# uC_HMI.net
KiCad netlist of a schematic drawn in Altium Designer
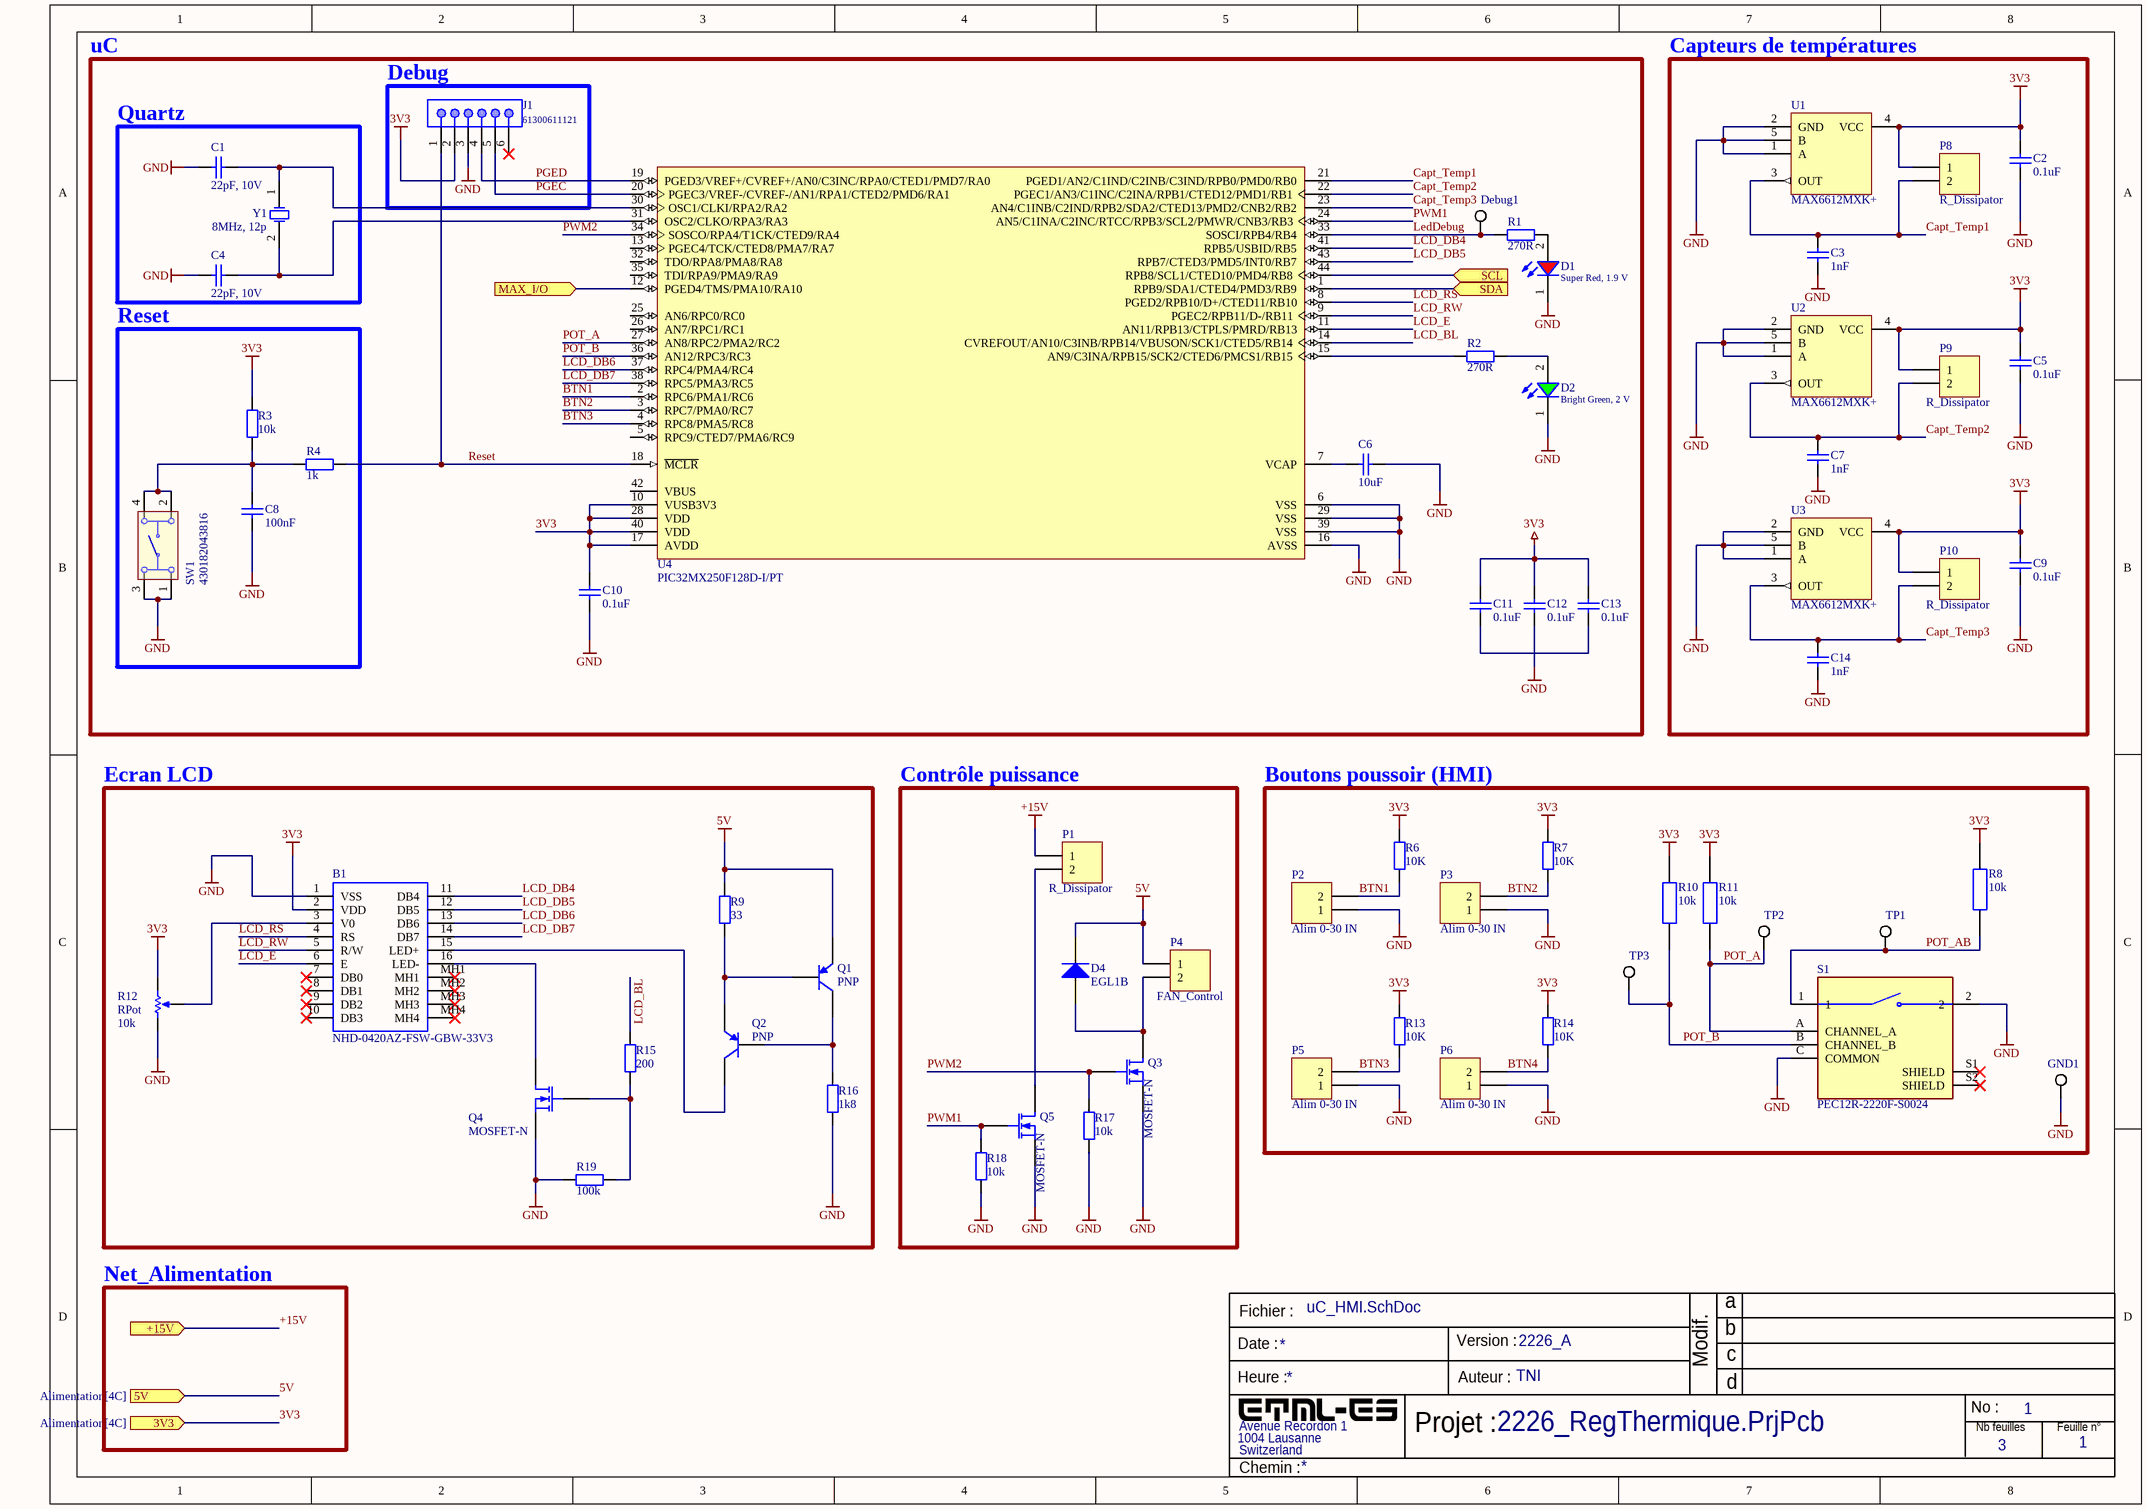
[diagram p0: uC_HMI.SchDoc]

(export (version "E")
  (design (tool "Eeschema 10.0.6"))
  (components
    (comp (ref "B1")
      (value "NHD-0420AZ-FSW-GBW-33V3")
      (footprint "NHD0420AZFSWGBW33V3")
      (description "LCD Character Display Modules & Accessories STN- GRAY Transfl 77.5 x 47.0")
      (fields (field (name "MOUSER PART NUMBER") "763-0420AZFSWGBW33V3"))
      (libsource (lib "NHD-0420AZ-FSW-GBW-33V3") (part "NHD-0420AZ-FSW-GBW-33V3"))
    )
    (comp (ref "C1")
      (value "22pF, 10V")
      (footprint "6-0805_L")
      (description "CAP 22pF 10V")
      (fields (field (name "TOLERANCE") "Â±10%"))
      (libsource (lib "2121_Robot3roues_V2.0") (part "CAP"))
    )
    (comp (ref "C2")
      (value "0.1uF")
      (footprint "C0805")
      (description "Cap 100nF")
      (fields (field (name "Comment") "Cap") (field (name "PUBLISHER") "Altium Limited"))
      (libsource (lib "Miscellaneous Devices") (part "Cap"))
    )
    (comp (ref "C3")
      (value "1nF")
      (footprint "C0805")
      (description "Cap 1nF")
      (fields (field (name "Comment") "Cap") (field (name "PUBLISHER") "Altium Limited"))
      (libsource (lib "Miscellaneous Devices") (part "Cap"))
    )
    (comp (ref "C4")
      (value "22pF, 10V")
      (footprint "6-0805_L")
      (description "CAP 22pF 10V")
      (fields (field (name "TOLERANCE") "Â±10%"))
      (libsource (lib "2121_Robot3roues_V2.0") (part "CAP"))
    )
    (comp (ref "C5")
      (value "0.1uF")
      (footprint "C0805")
      (description "Cap 100nF")
      (fields (field (name "Comment") "Cap") (field (name "PUBLISHER") "Altium Limited"))
      (libsource (lib "Miscellaneous Devices") (part "Cap"))
    )
    (comp (ref "C6")
      (value "10uF")
      (footprint "C0805")
      (description "Cap 100nF")
      (fields (field (name "Comment") "Cap") (field (name "PUBLISHER") "Altium Limited"))
      (libsource (lib "Miscellaneous Devices") (part "Cap"))
    )
    (comp (ref "C7")
      (value "1nF")
      (footprint "C0805")
      (description "Cap 1nF")
      (fields (field (name "Comment") "Cap") (field (name "PUBLISHER") "Altium Limited"))
      (libsource (lib "Miscellaneous Devices") (part "Cap"))
    )
    (comp (ref "C8")
      (value "100nF")
      (footprint "C0805")
      (description "Cap 100nF")
      (fields (field (name "Comment") "Cap") (field (name "PUBLISHER") "Altium Limited"))
      (libsource (lib "Miscellaneous Devices") (part "Cap"))
    )
    (comp (ref "C9")
      (value "0.1uF")
      (footprint "C0805")
      (description "Cap 100nF")
      (fields (field (name "Comment") "Cap") (field (name "PUBLISHER") "Altium Limited"))
      (libsource (lib "Miscellaneous Devices") (part "Cap"))
    )
    (comp (ref "C10")
      (value "0.1uF")
      (footprint "C0805")
      (description "Cap 100nF")
      (fields (field (name "Comment") "Cap") (field (name "PUBLISHER") "Altium Limited"))
      (libsource (lib "Miscellaneous Devices") (part "Cap"))
    )
    (comp (ref "C11")
      (value "0.1uF")
      (footprint "C0805")
      (description "Cap 100nF")
      (fields (field (name "Comment") "Cap") (field (name "PUBLISHER") "Altium Limited"))
      (libsource (lib "Miscellaneous Devices") (part "Cap"))
    )
    (comp (ref "C12")
      (value "0.1uF")
      (footprint "C0805")
      (description "Cap 100nF")
      (fields (field (name "Comment") "Cap") (field (name "PUBLISHER") "Altium Limited"))
      (libsource (lib "Miscellaneous Devices") (part "Cap"))
    )
    (comp (ref "C13")
      (value "0.1uF")
      (footprint "C0805")
      (description "Cap 100nF")
      (fields (field (name "Comment") "Cap") (field (name "PUBLISHER") "Altium Limited"))
      (libsource (lib "Miscellaneous Devices") (part "Cap"))
    )
    (comp (ref "C14")
      (value "1nF")
      (footprint "C0805")
      (description "Cap 1nF")
      (fields (field (name "Comment") "Cap") (field (name "PUBLISHER") "Altium Limited"))
      (libsource (lib "Miscellaneous Devices") (part "Cap"))
    )
    (comp (ref "D1")
      (value "Super Red, 1.9 V")
      (footprint "6-0805_N")
      (description "SMT Mono-color Chip LED Waterclear WL-SMCW, size 0805, Super Red, 1.9 V, 140 deg, 60 mcd")
      (fields (field (name "PART NUMBER") "150080SS75000") (field (name "PUBLISHER") "Wurth Elektronik"))
      (libsource (lib "VPA_v2b") (part "150080SS75000"))
    )
    (comp (ref "D2")
      (value "Bright Green, 2 V")
      (footprint "6-0805_N")
      (description "SMT Mono-color Chip LED Waterclear WL-SMCW, size 0805, Bright Green, 2 V, 140 deg, 40 mcd")
      (fields (field (name "PART NUMBER") "150080VS75000") (field (name "PUBLISHER") "Wurth Elektronik"))
      (libsource (lib "VPA_v2b") (part "150080VS75000"))
    )
    (comp (ref "D4")
      (value "EGL1B")
      (footprint "JAN1N4108CUR1_")
      (description "Diode Melf : EGL1B (100V,1A)")
      (fields (field (name "PUBLISHER") "Altium Limited"))
      (libsource (lib "Miscellaneous Devices") (part "Diode"))
    )
    (comp (ref "Debug1")
      (value "LedDebugg")
      (footprint "KSTN-5019_V")
      (description "Test Point, 1 Position SMD, RoHS, Tape and Reel")
      (libsource (lib "Altium Content Vault") (part "TESTPOINT_WHITE"))
    )
    (comp (ref "GND1")
      (value "PEC12")
      (footprint "KSTN-5019_V")
      (description "Test Point, 1 Position SMD, RoHS, Tape and Reel")
      (libsource (lib "Altium Content Vault") (part "TESTPOINT_WHITE"))
    )
    (comp (ref "J1")
      (value "61300611121")
      (footprint "HDR1X6")
      (description "WR-PHD Pin Header, THT, pitch 2.54mm, Single Row, Vertical, 6pin")
      (fields (field (name "PUBLISHER") "Wurth Elektronik"))
      (libsource (lib "VPA_v2b") (part "61300611121"))
    )
    (comp (ref "P1")
      (value "R_Dissipator")
      (footprint "RHDRRA2W95P0X500_1X2_1120X900X1280P")
      (description "Header, 2-Pin")
      (fields (field (name "PUBLISHER") "Altium Limited"))
      (libsource (lib "Miscellaneous Connectors") (part "Header 2"))
    )
    (comp (ref "P2")
      (value "Alim 0-30 IN")
      (footprint "HDR1X2")
      (description "Header, 2-Pin")
      (fields (field (name "PUBLISHER") "Altium Limited"))
      (libsource (lib "") (part "Header 2_1"))
    )
    (comp (ref "P3")
      (value "Alim 0-30 IN")
      (footprint "HDR1X2")
      (description "Header, 2-Pin")
      (fields (field (name "PUBLISHER") "Altium Limited"))
      (libsource (lib "") (part "Header 2_1"))
    )
    (comp (ref "P4")
      (value "FAN_Control")
      (footprint "RHDRRA2W95P0X500_1X2_1120X900X1280P")
      (description "Header, 2-Pin")
      (fields (field (name "PUBLISHER") "Altium Limited"))
      (libsource (lib "Miscellaneous Connectors") (part "Header 2"))
    )
    (comp (ref "P5")
      (value "Alim 0-30 IN")
      (footprint "HDR1X2")
      (description "Header, 2-Pin")
      (fields (field (name "PUBLISHER") "Altium Limited"))
      (libsource (lib "") (part "Header 2_1"))
    )
    (comp (ref "P6")
      (value "Alim 0-30 IN")
      (footprint "HDR1X2")
      (description "Header, 2-Pin")
      (fields (field (name "PUBLISHER") "Altium Limited"))
      (libsource (lib "") (part "Header 2_1"))
    )
    (comp (ref "P8")
      (value "R_Dissipator")
      (footprint "RHDRRA2W95P0X500_1X2_1120X900X1280P")
      (description "Header, 2-Pin")
      (fields (field (name "PUBLISHER") "Altium Limited"))
      (libsource (lib "Miscellaneous Connectors") (part "Header 2"))
    )
    (comp (ref "P9")
      (value "R_Dissipator")
      (footprint "RHDRRA2W95P0X500_1X2_1120X900X1280P")
      (description "Header, 2-Pin")
      (fields (field (name "PUBLISHER") "Altium Limited"))
      (libsource (lib "Miscellaneous Connectors") (part "Header 2"))
    )
    (comp (ref "P10")
      (value "R_Dissipator")
      (footprint "RHDRRA2W95P0X500_1X2_1120X900X1280P")
      (description "Header, 2-Pin")
      (fields (field (name "PUBLISHER") "Altium Limited"))
      (libsource (lib "Miscellaneous Connectors") (part "Header 2"))
    )
    (comp (ref "Q1")
      (value "PNP")
      (footprint "SOT-23B_N")
      (description "PNP Bipolar Transistor")
      (fields (field (name "PUBLISHER") "Altium Limited"))
      (libsource (lib "Miscellaneous Devices") (part "PNP"))
    )
    (comp (ref "Q2")
      (value "PNP")
      (footprint "SOT-23B_N")
      (description "PNP Bipolar Transistor")
      (fields (field (name "PUBLISHER") "Altium Limited"))
      (libsource (lib "Miscellaneous Devices") (part "PNP"))
    )
    (comp (ref "Q3")
      (value "MOSFET-N")
      (footprint "SOT23_N")
      (description "N-Channel MOSFET")
      (fields (field (name "PUBLISHER") "Altium Limited"))
      (libsource (lib "Miscellaneous Devices") (part "MOSFET-N"))
    )
    (comp (ref "Q4")
      (value "MOSFET-N")
      (footprint "SOT23_N")
      (description "N-Channel MOSFET")
      (fields (field (name "PUBLISHER") "Altium Limited"))
      (libsource (lib "Miscellaneous Devices") (part "MOSFET-N"))
    )
    (comp (ref "Q5")
      (value "MOSFET-N")
      (footprint "SOT23_N")
      (description "N-Channel MOSFET")
      (fields (field (name "PUBLISHER") "Altium Limited"))
      (libsource (lib "Miscellaneous Devices") (part "MOSFET-N"))
    )
    (comp (ref "R1")
      (value "270R")
      (footprint "6-0805_N")
      (description "Res 270R")
      (fields (field (name "PART NUMBER") "ERJ6ENF2703V") (field (name "MANUFACTURER") "Panasonic"))
      (libsource (lib "2121_Robot3roues_V2.0") (part "RES"))
    )
    (comp (ref "R2")
      (value "270R")
      (footprint "6-0805_N")
      (description "Res 270R")
      (fields (field (name "PART NUMBER") "ERJ6ENF2703V") (field (name "MANUFACTURER") "Panasonic"))
      (libsource (lib "2121_Robot3roues_V2.0") (part "RES"))
    )
    (comp (ref "R3")
      (value "10k")
      (footprint "6-0805_N")
      (description "Res 10K")
      (fields (field (name "MANUFACTURER") "Panasonic") (field (name "PART NUMBER") "ERJ-6ENF1002V"))
      (libsource (lib "") (part "RES_2"))
    )
    (comp (ref "R4")
      (value "1k")
      (footprint "6-0805_N")
      (description "Res 1K")
      (fields (field (name "PART NUMBER") "CRCW08051K00FKEA") (field (name "MANUFACTURER") "Vishay Dale"))
      (libsource (lib "") (part "RES_1"))
    )
    (comp (ref "R6")
      (value "10K")
      (footprint "6-0805_N")
      (description "Res 10K")
      (fields (field (name "PUBLISHER") "Altium Limited"))
      (libsource (lib "Miscellaneous Devices") (part "Res2"))
    )
    (comp (ref "R7")
      (value "10K")
      (footprint "6-0805_N")
      (description "Res 10K")
      (fields (field (name "PUBLISHER") "Altium Limited"))
      (libsource (lib "Miscellaneous Devices") (part "Res2"))
    )
    (comp (ref "R8")
      (value "10k")
      (footprint "6-0805_N")
      (description "Res 10K")
      (libsource (lib "2019_RegThermiqueMyRio") (part "Resistor"))
    )
    (comp (ref "R9")
      (value "33")
      (footprint "6-0805_N")
      (description "Res 33R")
      (fields (field (name "Comment") "Res2") (field (name "PUBLISHER") "Altium Limited"))
      (libsource (lib "") (part "Res2_2"))
    )
    (comp (ref "R10")
      (value "10k")
      (footprint "6-0805_N")
      (description "Res 10K")
      (libsource (lib "2019_RegThermiqueMyRio") (part "Resistor"))
    )
    (comp (ref "R11")
      (value "10k")
      (footprint "6-0805_N")
      (description "Res 10K")
      (libsource (lib "2019_RegThermiqueMyRio") (part "Resistor"))
    )
    (comp (ref "R12")
      (value "RPot")
      (footprint "3362P_1")
      (description "Pot 10K")
      (fields (field (name "ALTIUM_VALUE") "10k") (field (name "PUBLISHER") "Altium Limited"))
      (libsource (lib "Miscellaneous Devices") (part "RPot"))
    )
    (comp (ref "R13")
      (value "10K")
      (footprint "6-0805_N")
      (description "Res 10K")
      (fields (field (name "PUBLISHER") "Altium Limited"))
      (libsource (lib "Miscellaneous Devices") (part "Res2"))
    )
    (comp (ref "R14")
      (value "10K")
      (footprint "6-0805_N")
      (description "Res 10K")
      (fields (field (name "PUBLISHER") "Altium Limited"))
      (libsource (lib "Miscellaneous Devices") (part "Res2"))
    )
    (comp (ref "R15")
      (value "200")
      (footprint "6-0805_N")
      (description "Res 200R")
      (fields (field (name "Comment") "Res2") (field (name "PUBLISHER") "Altium Limited"))
      (libsource (lib "") (part "Res2_2"))
    )
    (comp (ref "R16")
      (value "1k8")
      (footprint "6-0805_N")
      (description "Res 1K8")
      (fields (field (name "Comment") "Res2") (field (name "PUBLISHER") "Altium Limited"))
      (libsource (lib "") (part "Res2_2"))
    )
    (comp (ref "R17")
      (value "10k")
      (footprint "6-0805_N")
      (description "Res 10K")
      (fields (field (name "Comment") "Res2") (field (name "PUBLISHER") "Altium Limited"))
      (libsource (lib "Miscellaneous Devices") (part "Res2"))
    )
    (comp (ref "R18")
      (value "10k")
      (footprint "6-0805_N")
      (description "Res 10K")
      (fields (field (name "Comment") "Res2") (field (name "PUBLISHER") "Altium Limited"))
      (libsource (lib "Miscellaneous Devices") (part "Res2"))
    )
    (comp (ref "R19")
      (value "100k")
      (footprint "6-0805_N")
      (description "Res 100K")
      (fields (field (name "Comment") "Res2") (field (name "PUBLISHER") "Altium Limited"))
      (libsource (lib "") (part "Res2_1"))
    )
    (comp (ref "S1")
      (value "PEC12R-2220F-S0024")
      (footprint "XDCR_PEC12R-2220F-S0024")
      (description "Rotary Encoder Mechanical 24 Quadrature (Incremental) Right Angle")
      (fields (field (name "MF") "Bourns"))
      (libsource (lib "2226_RegThermique") (part "PEC12R-2220F-S0024"))
    )
    (comp (ref "SW1")
      (value "430182043816")
      (footprint "430182043816")
      (description "WS-TASV SMD Tact Switch 6X6 mm")
      (fields (field (name "MANUFACTURER") "Wuerth Elektronik"))
      (libsource (lib "Altium Content Vault") (part "WE-TACT-SW-4"))
    )
    (comp (ref "TP1")
      (value "REGP")
      (footprint "KSTN-5019_V")
      (description "Test Point, 1 Position SMD, RoHS, Tape and Reel")
      (libsource (lib "Altium Content Vault") (part "TESTPOINT_WHITE"))
    )
    (comp (ref "TP2")
      (value "REGP")
      (footprint "KSTN-5019_V")
      (description "Test Point, 1 Position SMD, RoHS, Tape and Reel")
      (libsource (lib "Altium Content Vault") (part "TESTPOINT_WHITE"))
    )
    (comp (ref "TP3")
      (value "REGP")
      (footprint "KSTN-5019_V")
      (description "Test Point, 1 Position SMD, RoHS, Tape and Reel")
      (libsource (lib "Altium Content Vault") (part "TESTPOINT_WHITE"))
    )
    (comp (ref "U1")
      (value "MAX6612MXK+")
      (footprint "MAXM-X5+1_M")
      (description "High-Slope, Low-Power, Analog Temperature Sensor, -55 to 150 degC, 5-Pin SOT23 (X5+1), Pb-Free")
      (fields (field (name "GENERIC PART NUMBER") "MAX6612"))
      (libsource (lib "Altium Content Vault") (part "MAX6612-X5"))
    )
    (comp (ref "U2")
      (value "MAX6612MXK+")
      (footprint "MAXM-X5+1_M")
      (description "High-Slope, Low-Power, Analog Temperature Sensor, -55 to 150 degC, 5-Pin SOT23 (X5+1), Pb-Free")
      (fields (field (name "GENERIC PART NUMBER") "MAX6612"))
      (libsource (lib "Altium Content Vault") (part "MAX6612-X5"))
    )
    (comp (ref "U3")
      (value "MAX6612MXK+")
      (footprint "MAXM-X5+1_M")
      (description "High-Slope, Low-Power, Analog Temperature Sensor, -55 to 150 degC, 5-Pin SOT23 (X5+1), Pb-Free")
      (fields (field (name "GENERIC PART NUMBER") "MAX6612"))
      (libsource (lib "Altium Content Vault") (part "MAX6612-X5"))
    )
    (comp (ref "U4")
      (value "PIC32MX250F128D-I/PT")
      (footprint "MCHP-TQFP-PT44_M")
      (fields (field (name "MANUFACTURER") "Microchip"))
      (libsource (lib "Altium Content Vault") (part "MCHP-PIC32MX2XXFXXXD-TQFP-44"))
    )
    (comp (ref "Y1")
      (value "8MHz, 12p")
      (footprint "FOX-FOXSDLF160-20_V")
      (libsource (lib "Altium Content Vault") (part "XTAL_1-2-2"))
    )
  )
  (nets
    (net (code "1") (name "+15V") (class "Default")
      (node (ref "P1") (pin "1") (pinfunction "1_1") (pintype "passive"))
    )
    (net (code "2") (name "/BTN1") (class "Default")
      (node (ref "P2") (pin "2") (pinfunction "2_2") (pintype "passive"))
      (node (ref "R6") (pin "1") (pinfunction "1_1") (pintype "passive"))
      (node (ref "U4") (pin "2") (pinfunction "RPC6/PMA1/RC6_2") (pintype "bidirectional"))
    )
    (net (code "3") (name "/BTN2") (class "Default")
      (node (ref "P3") (pin "2") (pinfunction "2_2") (pintype "passive"))
      (node (ref "R7") (pin "1") (pinfunction "1_1") (pintype "passive"))
      (node (ref "U4") (pin "3") (pinfunction "RPC7/PMA0/RC7_3") (pintype "bidirectional"))
    )
    (net (code "4") (name "/BTN3") (class "Default")
      (node (ref "P5") (pin "2") (pinfunction "2_2") (pintype "passive"))
      (node (ref "R13") (pin "1") (pinfunction "1_1") (pintype "passive"))
      (node (ref "U4") (pin "4") (pinfunction "RPC8/PMA5/RC8_4") (pintype "bidirectional"))
    )
    (net (code "5") (name "/BTN4") (class "Default")
      (node (ref "P6") (pin "2") (pinfunction "2_2") (pintype "passive"))
      (node (ref "R14") (pin "1") (pinfunction "1_1") (pintype "passive"))
    )
    (net (code "6") (name "/Capt_Temp1") (class "Default")
      (node (ref "C3") (pin "1") (pinfunction "1_1") (pintype "passive"))
      (node (ref "P8") (pin "2") (pinfunction "2_2") (pintype "passive"))
      (node (ref "U1") (pin "3") (pinfunction "OUT_3") (pintype "output"))
      (node (ref "U4") (pin "21") (pinfunction "PGED1/AN2/C1IND/C2INB/C3IND/RPB0/PMD0/RB0_21") (pintype "passive"))
    )
    (net (code "7") (name "/Capt_Temp2") (class "Default")
      (node (ref "C7") (pin "1") (pinfunction "1_1") (pintype "passive"))
      (node (ref "P9") (pin "2") (pinfunction "2_2") (pintype "passive"))
      (node (ref "U2") (pin "3") (pinfunction "OUT_3") (pintype "output"))
      (node (ref "U4") (pin "22") (pinfunction "PGEC1/AN3/C1INC/C2INA/RPB1/CTED12/PMD1/RB1_22") (pintype "passive"))
    )
    (net (code "8") (name "/Capt_Temp3") (class "Default")
      (node (ref "C14") (pin "1") (pinfunction "1_1") (pintype "passive"))
      (node (ref "P10") (pin "2") (pinfunction "2_2") (pintype "passive"))
      (node (ref "U3") (pin "3") (pinfunction "OUT_3") (pintype "output"))
      (node (ref "U4") (pin "23") (pinfunction "AN4/C1INB/C2IND/RPB2/SDA2/CTED13/PMD2/CNB2/RB2_23") (pintype "passive"))
    )
    (net (code "9") (name "/LCD_BL") (class "Default")
      (node (ref "R15") (pin "1") (pinfunction "1_1") (pintype "passive"))
      (node (ref "U4") (pin "14") (pinfunction "CVREFOUT/AN10/C3INB/RPB14/VBUSON/SCK1/CTED5/RB14_14") (pintype "bidirectional"))
    )
    (net (code "10") (name "/LCD_DB4") (class "Default")
      (node (ref "B1") (pin "11") (pinfunction "DB4_11") (pintype "passive"))
      (node (ref "U4") (pin "41") (pinfunction "RPB5/USBID/RB5_41") (pintype "bidirectional"))
    )
    (net (code "11") (name "/LCD_DB5") (class "Default")
      (node (ref "B1") (pin "12") (pinfunction "DB5_12") (pintype "passive"))
      (node (ref "U4") (pin "43") (pinfunction "RPB7/CTED3/PMD5/INT0/RB7_43") (pintype "bidirectional"))
    )
    (net (code "12") (name "/LCD_DB6") (class "Default")
      (node (ref "B1") (pin "13") (pinfunction "DB6_13") (pintype "passive"))
      (node (ref "U4") (pin "37") (pinfunction "RPC4/PMA4/RC4_37") (pintype "bidirectional"))
    )
    (net (code "13") (name "/LCD_DB7") (class "Default")
      (node (ref "B1") (pin "14") (pinfunction "DB7_14") (pintype "passive"))
      (node (ref "U4") (pin "38") (pinfunction "RPC5/PMA3/RC5_38") (pintype "bidirectional"))
    )
    (net (code "14") (name "/LCD_E") (class "Default")
      (node (ref "B1") (pin "6") (pinfunction "E_6") (pintype "passive"))
      (node (ref "U4") (pin "11") (pinfunction "AN11/RPB13/CTPLS/PMRD/RB13_11") (pintype "bidirectional"))
    )
    (net (code "15") (name "/LCD_RS") (class "Default")
      (node (ref "B1") (pin "4") (pinfunction "RS_4") (pintype "passive"))
      (node (ref "U4") (pin "8") (pinfunction "PGED2/RPB10/D+/CTED11/RB10_8") (pintype "bidirectional"))
    )
    (net (code "16") (name "/LCD_RW") (class "Default")
      (node (ref "B1") (pin "5") (pinfunction "R/W_5") (pintype "passive"))
      (node (ref "U4") (pin "9") (pinfunction "PGEC2/RPB11/D-/RB11_9") (pintype "bidirectional"))
    )
    (net (code "17") (name "/LedDebug") (class "Default")
      (node (ref "Debug1") (pin "1") (pinfunction "1_1") (pintype "passive"))
      (node (ref "R1") (pin "2") (pinfunction "2_2") (pintype "passive"))
      (node (ref "U4") (pin "33") (pinfunction "SOSCI/RPB4/RB4_33") (pintype "bidirectional"))
    )
    (net (code "18") (name "/MAX_I{slash}O") (class "Default")
      (node (ref "U4") (pin "12") (pinfunction "PGED4/TMS/PMA10/RA10_12") (pintype "bidirectional"))
    )
    (net (code "19") (name "/PGEC") (class "Default")
      (node (ref "J1") (pin "5") (pinfunction "5_5") (pintype "passive"))
      (node (ref "U4") (pin "20") (pinfunction "PGEC3/VREF-/CVREF-/AN1/RPA1/CTED2/PMD6/RA1_20") (pintype "bidirectional"))
    )
    (net (code "20") (name "/PGED") (class "Default")
      (node (ref "J1") (pin "4") (pinfunction "4_4") (pintype "passive"))
      (node (ref "U4") (pin "19") (pinfunction "PGED3/VREF+/CVREF+/AN0/C3INC/RPA0/CTED1/PMD7/RA0_19") (pintype "bidirectional"))
    )
    (net (code "21") (name "/POT_A") (class "Default")
      (node (ref "R11") (pin "1") (pinfunction "1_1") (pintype "passive"))
      (node (ref "S1") (pin "A") (pinfunction "CHANNEL_A_A") (pintype "passive"))
      (node (ref "TP2") (pin "1") (pinfunction "1_1") (pintype "passive"))
      (node (ref "U4") (pin "27") (pinfunction "AN8/RPC2/PMA2/RC2_27") (pintype "bidirectional"))
    )
    (net (code "22") (name "/POT_AB") (class "Default")
      (node (ref "R8") (pin "1") (pinfunction "1_1") (pintype "passive"))
      (node (ref "S1") (pin "1") (pinfunction "1_1") (pintype "passive"))
      (node (ref "TP1") (pin "1") (pinfunction "1_1") (pintype "passive"))
    )
    (net (code "23") (name "/POT_B") (class "Default")
      (node (ref "R10") (pin "1") (pinfunction "1_1") (pintype "passive"))
      (node (ref "S1") (pin "B") (pinfunction "CHANNEL_B_B") (pintype "passive"))
      (node (ref "TP3") (pin "1") (pinfunction "1_1") (pintype "passive"))
      (node (ref "U4") (pin "36") (pinfunction "AN12/RPC3/RC3_36") (pintype "bidirectional"))
    )
    (net (code "24") (name "/PWM1") (class "Default")
      (node (ref "Q5") (pin "2") (pinfunction "G_2") (pintype "passive"))
      (node (ref "R18") (pin "2") (pinfunction "2_2") (pintype "passive"))
      (node (ref "U4") (pin "24") (pinfunction "AN5/C1INA/C2INC/RTCC/RPB3/SCL2/PMWR/CNB3/RB3_24") (pintype "bidirectional"))
    )
    (net (code "25") (name "/PWM2") (class "Default")
      (node (ref "Q3") (pin "2") (pinfunction "G_2") (pintype "passive"))
      (node (ref "R17") (pin "2") (pinfunction "2_2") (pintype "passive"))
      (node (ref "U4") (pin "34") (pinfunction "SOSCO/RPA4/T1CK/CTED9/RA4_34") (pintype "bidirectional"))
    )
    (net (code "26") (name "/Reset") (class "Default")
      (node (ref "J1") (pin "1") (pinfunction "1_1") (pintype "passive"))
      (node (ref "R4") (pin "2") (pinfunction "2_2") (pintype "passive"))
      (node (ref "U4") (pin "18") (pinfunction "~{MCLR}_18") (pintype "input"))
    )
    (net (code "27") (name "/SCL") (class "Default")
      (node (ref "U4") (pin "44") (pinfunction "RPB8/SCL1/CTED10/PMD4/RB8_44") (pintype "bidirectional"))
    )
    (net (code "28") (name "/SDA") (class "Default")
      (node (ref "U4") (pin "1") (pinfunction "RPB9/SDA1/CTED4/PMD3/RB9_1") (pintype "bidirectional"))
    )
    (net (code "29") (name "3V3") (class "Default")
      (node (ref "B1") (pin "2") (pinfunction "VDD_2") (pintype "passive"))
      (node (ref "C10") (pin "2") (pinfunction "2_2") (pintype "passive"))
      (node (ref "C11") (pin "1") (pinfunction "1_1") (pintype "passive"))
      (node (ref "C12") (pin "1") (pinfunction "1_1") (pintype "passive"))
      (node (ref "C13") (pin "1") (pinfunction "1_1") (pintype "passive"))
      (node (ref "C2") (pin "1") (pinfunction "1_1") (pintype "passive"))
      (node (ref "C5") (pin "1") (pinfunction "1_1") (pintype "passive"))
      (node (ref "C9") (pin "1") (pinfunction "1_1") (pintype "passive"))
      (node (ref "J1") (pin "2") (pinfunction "2_2") (pintype "passive"))
      (node (ref "P10") (pin "1") (pinfunction "1_1") (pintype "passive"))
      (node (ref "P8") (pin "1") (pinfunction "1_1") (pintype "passive"))
      (node (ref "P9") (pin "1") (pinfunction "1_1") (pintype "passive"))
      (node (ref "R10") (pin "2") (pinfunction "2_2") (pintype "passive"))
      (node (ref "R11") (pin "2") (pinfunction "2_2") (pintype "passive"))
      (node (ref "R12") (pin "2") (pinfunction "BOT_2") (pintype "passive"))
      (node (ref "R13") (pin "2") (pinfunction "2_2") (pintype "passive"))
      (node (ref "R14") (pin "2") (pinfunction "2_2") (pintype "passive"))
      (node (ref "R3") (pin "2") (pinfunction "2_2") (pintype "passive"))
      (node (ref "R6") (pin "2") (pinfunction "2_2") (pintype "passive"))
      (node (ref "R7") (pin "2") (pinfunction "2_2") (pintype "passive"))
      (node (ref "R8") (pin "2") (pinfunction "2_2") (pintype "passive"))
      (node (ref "U1") (pin "4") (pinfunction "VCC_4") (pintype "passive"))
      (node (ref "U2") (pin "4") (pinfunction "VCC_4") (pintype "passive"))
      (node (ref "U3") (pin "4") (pinfunction "VCC_4") (pintype "passive"))
      (node (ref "U4") (pin "10") (pinfunction "VUSB3V3_10") (pintype "passive"))
      (node (ref "U4") (pin "17") (pinfunction "AVDD_17") (pintype "power_in"))
      (node (ref "U4") (pin "28") (pinfunction "VDD_28") (pintype "passive"))
      (node (ref "U4") (pin "40") (pinfunction "VDD_40") (pintype "passive"))
    )
    (net (code "30") (name "5V") (class "Default")
      (node (ref "D4") (pin "2") (pinfunction "K_2") (pintype "passive"))
      (node (ref "P4") (pin "1") (pinfunction "1_1") (pintype "passive"))
      (node (ref "Q1") (pin "3") (pinfunction "E_3") (pintype "passive"))
      (node (ref "R9") (pin "1") (pinfunction "1_1") (pintype "passive"))
    )
    (net (code "31") (name "GND") (class "Default")
      (node (ref "B1") (pin "1") (pinfunction "VSS_1") (pintype "passive"))
      (node (ref "C1") (pin "1") (pinfunction "1_1") (pintype "passive"))
      (node (ref "C10") (pin "1") (pinfunction "1_1") (pintype "passive"))
      (node (ref "C12") (pin "2") (pinfunction "2_2") (pintype "passive"))
      (node (ref "C14") (pin "2") (pinfunction "2_2") (pintype "passive"))
      (node (ref "C2") (pin "2") (pinfunction "2_2") (pintype "passive"))
      (node (ref "C3") (pin "2") (pinfunction "2_2") (pintype "passive"))
      (node (ref "C4") (pin "1") (pinfunction "1_1") (pintype "passive"))
      (node (ref "C5") (pin "2") (pinfunction "2_2") (pintype "passive"))
      (node (ref "C6") (pin "1") (pinfunction "1_1") (pintype "passive"))
      (node (ref "C7") (pin "2") (pinfunction "2_2") (pintype "passive"))
      (node (ref "C8") (pin "2") (pinfunction "2_2") (pintype "passive"))
      (node (ref "C9") (pin "2") (pinfunction "2_2") (pintype "passive"))
      (node (ref "D1") (pin "1") (pinfunction "K_1") (pintype "passive"))
      (node (ref "D2") (pin "1") (pinfunction "K_1") (pintype "passive"))
      (node (ref "GND1") (pin "1") (pinfunction "1_1") (pintype "passive"))
      (node (ref "J1") (pin "3") (pinfunction "3_3") (pintype "passive"))
      (node (ref "P2") (pin "1") (pinfunction "1_1") (pintype "passive"))
      (node (ref "P3") (pin "1") (pinfunction "1_1") (pintype "passive"))
      (node (ref "P5") (pin "1") (pinfunction "1_1") (pintype "passive"))
      (node (ref "P6") (pin "1") (pinfunction "1_1") (pintype "passive"))
      (node (ref "Q3") (pin "3") (pinfunction "S_3") (pintype "passive"))
      (node (ref "Q4") (pin "3") (pinfunction "S_3") (pintype "passive"))
      (node (ref "Q5") (pin "3") (pinfunction "S_3") (pintype "passive"))
      (node (ref "R12") (pin "1") (pinfunction "TOP_1") (pintype "passive"))
      (node (ref "R16") (pin "2") (pinfunction "2_2") (pintype "passive"))
      (node (ref "R17") (pin "1") (pinfunction "1_1") (pintype "passive"))
      (node (ref "R18") (pin "1") (pinfunction "1_1") (pintype "passive"))
      (node (ref "R19") (pin "1") (pinfunction "1_1") (pintype "passive"))
      (node (ref "S1") (pin "2") (pinfunction "2_2") (pintype "passive"))
      (node (ref "S1") (pin "C") (pinfunction "COMMON_C") (pintype "passive"))
      (node (ref "SW1") (pin "1") (pinfunction "1_1") (pintype "passive"))
      (node (ref "SW1") (pin "3") (pinfunction "3_3") (pintype "passive"))
      (node (ref "U1") (pin "1") (pinfunction "A_1") (pintype "power_in"))
      (node (ref "U1") (pin "2") (pinfunction "GND_2") (pintype "power_in"))
      (node (ref "U1") (pin "5") (pinfunction "B_5") (pintype "power_in"))
      (node (ref "U2") (pin "1") (pinfunction "A_1") (pintype "power_in"))
      (node (ref "U2") (pin "2") (pinfunction "GND_2") (pintype "power_in"))
      (node (ref "U2") (pin "5") (pinfunction "B_5") (pintype "power_in"))
      (node (ref "U3") (pin "1") (pinfunction "A_1") (pintype "power_in"))
      (node (ref "U3") (pin "2") (pinfunction "GND_2") (pintype "power_in"))
      (node (ref "U3") (pin "5") (pinfunction "B_5") (pintype "power_in"))
      (node (ref "U4") (pin "16") (pinfunction "AVSS_16") (pintype "power_in"))
      (node (ref "U4") (pin "29") (pinfunction "VSS_29") (pintype "power_in"))
      (node (ref "U4") (pin "39") (pinfunction "VSS_39") (pintype "power_in"))
      (node (ref "U4") (pin "6") (pinfunction "VSS_6") (pintype "power_in"))
    )
    (net (code "32") (name "Net-(B1-LED+)") (class "Default")
      (node (ref "B1") (pin "15") (pinfunction "LED+_15") (pintype "passive"))
      (node (ref "Q2") (pin "1") (pinfunction "C_1") (pintype "passive"))
    )
    (net (code "33") (name "Net-(B1-LED-)") (class "Default")
      (node (ref "B1") (pin "16") (pinfunction "LED-_16") (pintype "passive"))
      (node (ref "Q4") (pin "1") (pinfunction "D_1") (pintype "passive"))
    )
    (net (code "34") (name "Net-(B1-V0)") (class "Default")
      (node (ref "B1") (pin "3") (pinfunction "V0_3") (pintype "passive"))
      (node (ref "R12") (pin "3") (pinfunction "TAP_3") (pintype "passive"))
    )
    (net (code "35") (name "Net-(C8-Pad1)") (class "Default")
      (node (ref "C8") (pin "1") (pinfunction "1_1") (pintype "passive"))
      (node (ref "R3") (pin "1") (pinfunction "1_1") (pintype "passive"))
      (node (ref "R4") (pin "1") (pinfunction "1_1") (pintype "passive"))
      (node (ref "SW1") (pin "2") (pinfunction "2_2") (pintype "passive"))
      (node (ref "SW1") (pin "4") (pinfunction "4_4") (pintype "passive"))
    )
    (net (code "36") (name "Net-(C11-Pad2)") (class "Default")
      (node (ref "C11") (pin "2") (pinfunction "2_2") (pintype "passive"))
      (node (ref "C13") (pin "2") (pinfunction "2_2") (pintype "passive"))
    )
    (net (code "37") (name "Net-(D1-A)") (class "Default")
      (node (ref "D1") (pin "2") (pinfunction "A_2") (pintype "passive"))
      (node (ref "R1") (pin "1") (pinfunction "1_1") (pintype "passive"))
    )
    (net (code "38") (name "Net-(D2-A)") (class "Default")
      (node (ref "D2") (pin "2") (pinfunction "A_2") (pintype "passive"))
      (node (ref "R2") (pin "1") (pinfunction "1_1") (pintype "passive"))
    )
    (net (code "39") (name "Net-(D4-A)") (class "Default")
      (node (ref "D4") (pin "1") (pinfunction "A_1") (pintype "passive"))
      (node (ref "P4") (pin "2") (pinfunction "2_2") (pintype "passive"))
      (node (ref "Q3") (pin "1") (pinfunction "D_1") (pintype "passive"))
    )
    (net (code "40") (name "Net-(Q1-B)") (class "Default")
      (node (ref "Q1") (pin "2") (pinfunction "B_2") (pintype "passive"))
      (node (ref "Q2") (pin "3") (pinfunction "E_3") (pintype "passive"))
      (node (ref "R9") (pin "2") (pinfunction "2_2") (pintype "passive"))
    )
    (net (code "41") (name "Net-(Q1-C)") (class "Default")
      (node (ref "Q1") (pin "1") (pinfunction "C_1") (pintype "passive"))
      (node (ref "Q2") (pin "2") (pinfunction "B_2") (pintype "passive"))
      (node (ref "R16") (pin "1") (pinfunction "1_1") (pintype "passive"))
    )
    (net (code "42") (name "Net-(Q4-G)") (class "Default")
      (node (ref "Q4") (pin "2") (pinfunction "G_2") (pintype "passive"))
      (node (ref "R15") (pin "2") (pinfunction "2_2") (pintype "passive"))
      (node (ref "R19") (pin "2") (pinfunction "2_2") (pintype "passive"))
    )
    (net (code "43") (name "Net-(Q5-D)") (class "Default")
      (node (ref "P1") (pin "2") (pinfunction "2_2") (pintype "passive"))
      (node (ref "Q5") (pin "1") (pinfunction "D_1") (pintype "passive"))
    )
    (net (code "44") (name "Net-(U4-AN9{slash}C3INA{slash}RPB15{slash}SCK2{slash}CTED6{slash}PMCS1{slash}RB15)") (class "Default")
      (node (ref "R2") (pin "2") (pinfunction "2_2") (pintype "passive"))
      (node (ref "U4") (pin "15") (pinfunction "AN9/C3INA/RPB15/SCK2/CTED6/PMCS1/RB15_15") (pintype "bidirectional"))
    )
    (net (code "45") (name "Net-(U4-OSC1{slash}CLKI{slash}RPA2{slash}RA2)") (class "Default")
      (node (ref "C1") (pin "2") (pinfunction "2_2") (pintype "passive"))
      (node (ref "U4") (pin "30") (pinfunction "OSC1/CLKI/RPA2/RA2_30") (pintype "bidirectional"))
      (node (ref "Y1") (pin "1") (pinfunction "X1_1") (pintype "passive"))
    )
    (net (code "46") (name "Net-(U4-OSC2{slash}CLKO{slash}RPA3{slash}RA3)") (class "Default")
      (node (ref "C4") (pin "2") (pinfunction "2_2") (pintype "passive"))
      (node (ref "U4") (pin "31") (pinfunction "OSC2/CLKO/RPA3/RA3_31") (pintype "bidirectional"))
      (node (ref "Y1") (pin "2") (pinfunction "X2_2") (pintype "passive"))
    )
    (net (code "47") (name "Net-(U4-VCAP)") (class "Default")
      (node (ref "C6") (pin "2") (pinfunction "2_2") (pintype "passive"))
      (node (ref "U4") (pin "7") (pinfunction "VCAP_7") (pintype "passive"))
    )
    (net (code "48") (name "unconnected-(B1-DB0-Pad7)") (class "Default")
      (node (ref "B1") (pin "7") (pinfunction "DB0_7") (pintype "passive+no_connect"))
    )
    (net (code "49") (name "unconnected-(B1-DB1-Pad8)") (class "Default")
      (node (ref "B1") (pin "8") (pinfunction "DB1_8") (pintype "passive+no_connect"))
    )
    (net (code "50") (name "unconnected-(B1-DB2-Pad9)") (class "Default")
      (node (ref "B1") (pin "9") (pinfunction "DB2_9") (pintype "passive+no_connect"))
    )
    (net (code "51") (name "unconnected-(B1-DB3-Pad10)") (class "Default")
      (node (ref "B1") (pin "10") (pinfunction "DB3_10") (pintype "passive+no_connect"))
    )
    (net (code "52") (name "unconnected-(B1-PadMH1)") (class "Default")
      (node (ref "B1") (pin "MH1") (pinfunction "MH1_MH1") (pintype "passive+no_connect"))
    )
    (net (code "53") (name "unconnected-(B1-PadMH2)") (class "Default")
      (node (ref "B1") (pin "MH2") (pinfunction "MH2_MH2") (pintype "passive+no_connect"))
    )
    (net (code "54") (name "unconnected-(B1-PadMH3)") (class "Default")
      (node (ref "B1") (pin "MH3") (pinfunction "MH3_MH3") (pintype "passive+no_connect"))
    )
    (net (code "55") (name "unconnected-(B1-PadMH4)") (class "Default")
      (node (ref "B1") (pin "MH4") (pinfunction "MH4_MH4") (pintype "passive+no_connect"))
    )
    (net (code "56") (name "unconnected-(J1-Pad6)") (class "Default")
      (node (ref "J1") (pin "6") (pinfunction "6_6") (pintype "passive+no_connect"))
    )
    (net (code "57") (name "unconnected-(S1-SHIELD-PadS1)") (class "Default")
      (node (ref "S1") (pin "S1") (pinfunction "SHIELD_S1") (pintype "passive+no_connect"))
    )
    (net (code "58") (name "unconnected-(S1-SHIELD-PadS2)") (class "Default")
      (node (ref "S1") (pin "S2") (pinfunction "SHIELD_S2") (pintype "passive+no_connect"))
    )
    (net (code "59") (name "unconnected-(U4-AN6{slash}RPC0{slash}RC0-Pad25)") (class "Default")
      (node (ref "U4") (pin "25") (pinfunction "AN6/RPC0/RC0_25") (pintype "bidirectional"))
    )
    (net (code "60") (name "unconnected-(U4-AN7{slash}RPC1{slash}RC1-Pad26)") (class "Default")
      (node (ref "U4") (pin "26") (pinfunction "AN7/RPC1/RC1_26") (pintype "bidirectional"))
    )
    (net (code "61") (name "unconnected-(U4-PGEC4{slash}TCK{slash}CTED8{slash}PMA7{slash}RA7-Pad13)") (class "Default")
      (node (ref "U4") (pin "13") (pinfunction "PGEC4/TCK/CTED8/PMA7/RA7_13") (pintype "bidirectional"))
    )
    (net (code "62") (name "unconnected-(U4-RPC9{slash}CTED7{slash}PMA6{slash}RC9-Pad5)") (class "Default")
      (node (ref "U4") (pin "5") (pinfunction "RPC9/CTED7/PMA6/RC9_5") (pintype "bidirectional"))
    )
    (net (code "63") (name "unconnected-(U4-TDI{slash}RPA9{slash}PMA9{slash}RA9-Pad35)") (class "Default")
      (node (ref "U4") (pin "35") (pinfunction "TDI/RPA9/PMA9/RA9_35") (pintype "bidirectional"))
    )
    (net (code "64") (name "unconnected-(U4-TDO{slash}RPA8{slash}PMA8{slash}RA8-Pad32)") (class "Default")
      (node (ref "U4") (pin "32") (pinfunction "TDO/RPA8/PMA8/RA8_32") (pintype "bidirectional"))
    )
    (net (code "65") (name "unconnected-(U4-VBUS-Pad42)") (class "Default")
      (node (ref "U4") (pin "42") (pinfunction "VBUS_42") (pintype "power_in"))
    )
  )
)
